# Meaty_3__vPS01.net
KiCad netlist of a schematic drawn in EAGLE
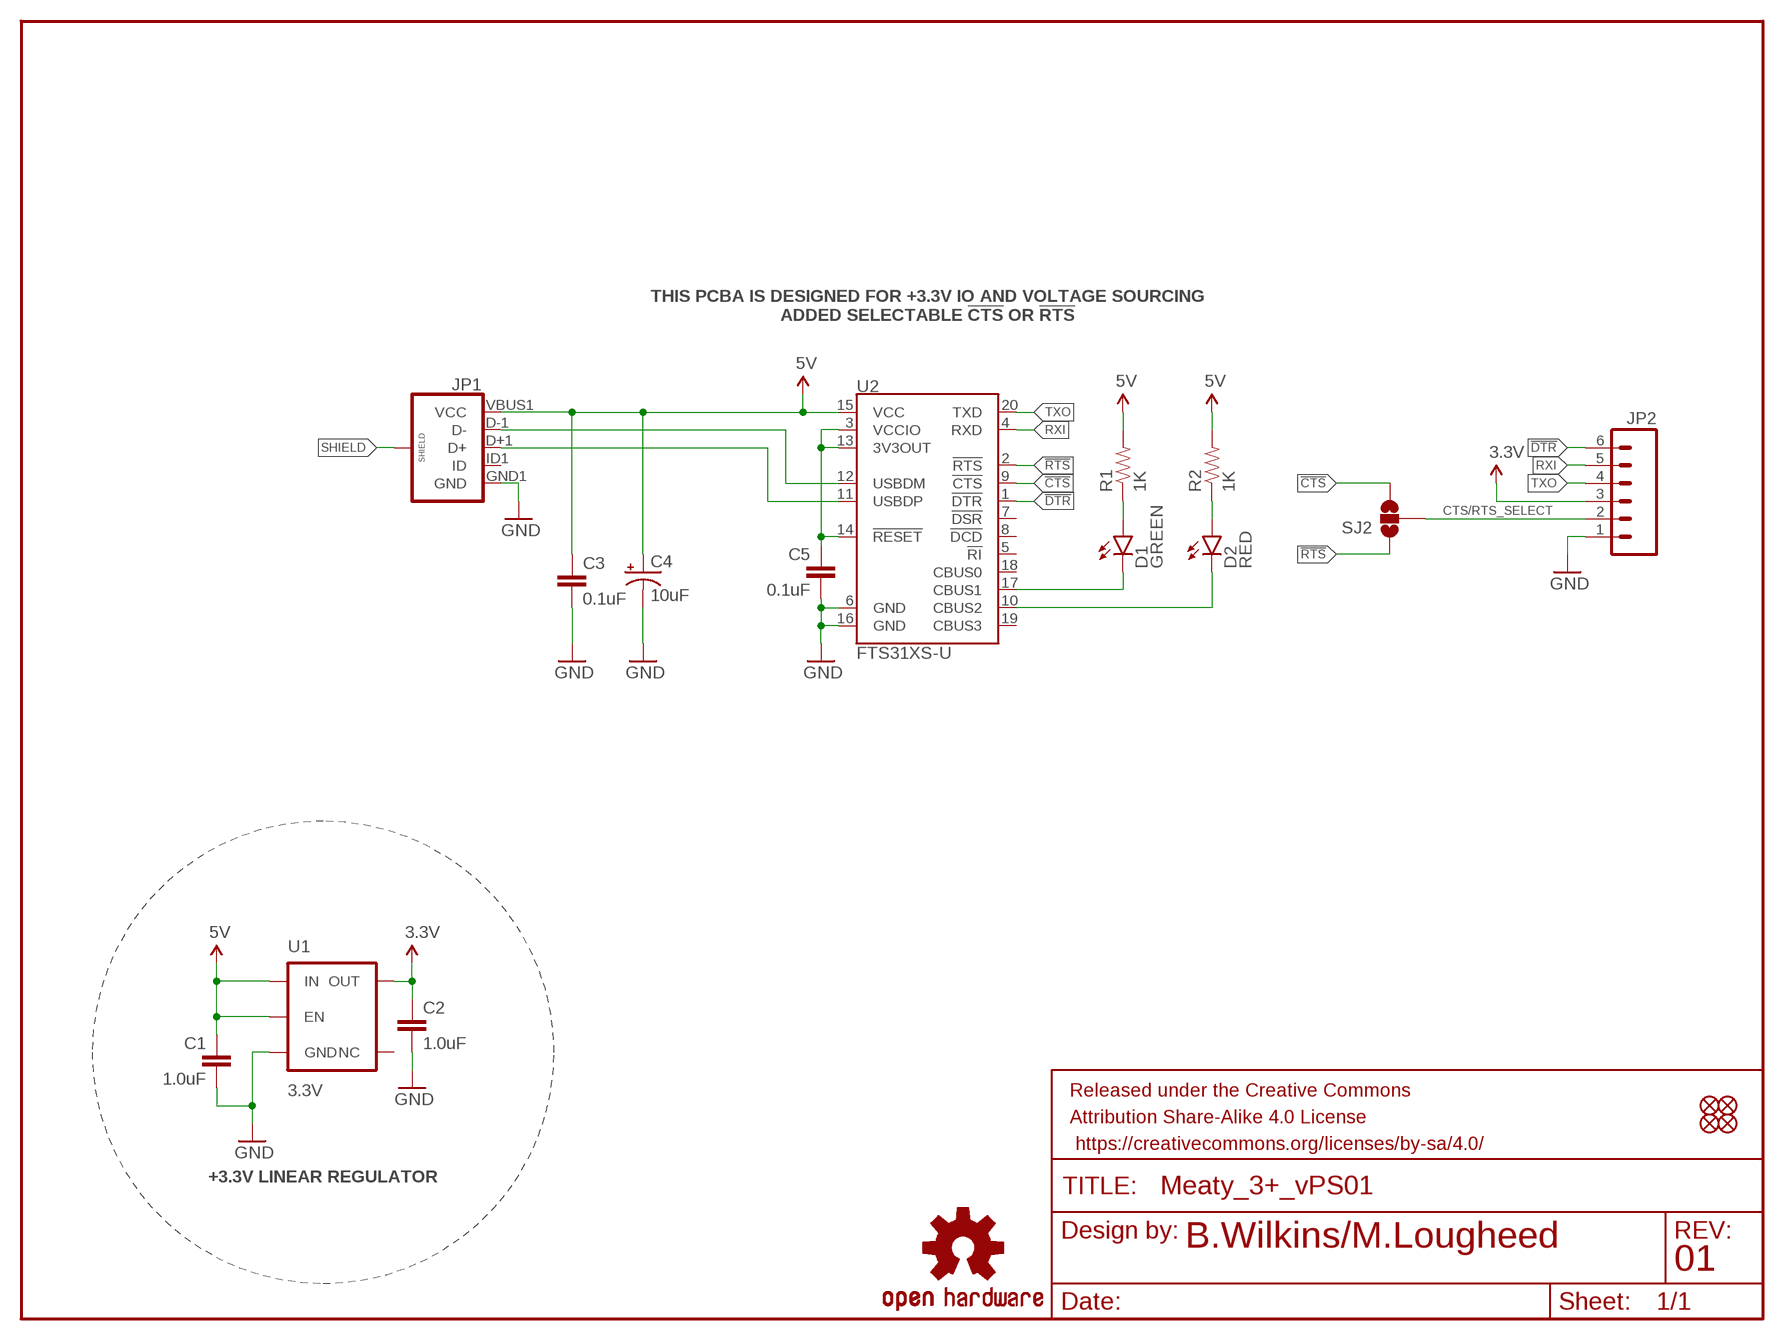
[diagram p0: schematic, sheet 1]

(export (version "E")
  (design (tool "Eeschema 10.0.6"))
  (components
    (comp (ref "C1")
      (value "1.0uF")
      (footprint "eagle-import:0603-CAP")
      (libsource (lib "eagle-import") (part "1.0UF-16V-10%(0603)"))
    )
    (comp (ref "C2")
      (value "1.0uF")
      (footprint "eagle-import:0603-CAP")
      (libsource (lib "eagle-import") (part "1.0UF-16V-10%(0603)"))
    )
    (comp (ref "C3")
      (value "0.1uF")
      (footprint "eagle-import:0603-CAP")
      (libsource (lib "eagle-import") (part "0.1UF-25V(+80/-20%)(0603)"))
    )
    (comp (ref "C4")
      (value "10uF")
      (footprint "eagle-import:EIA3216")
      (libsource (lib "eagle-import") (part "10UF-16V-10%(TANT)"))
    )
    (comp (ref "C5")
      (value "0.1uF")
      (footprint "eagle-import:0603-CAP")
      (libsource (lib "eagle-import") (part "0.1UF-25V(+80/-20%)(0603)"))
    )
    (comp (ref "D1")
      (value "GREEN")
      (footprint "eagle-import:LED-0603")
      (libsource (lib "eagle-import") (part "LED-GREEN0603"))
    )
    (comp (ref "D2")
      (value "RED")
      (footprint "eagle-import:LED-0603")
      (libsource (lib "eagle-import") (part "LED-RED0603"))
    )
    (comp (ref "FRAME1")
      (value "FRAME-LETTER")
      (footprint "eagle-import:CREATIVE_COMMONS")
      (libsource (lib "eagle-import") (part "FRAME-LETTER"))
    )
    (comp (ref "JP1")
      (value "USB_MICROB_PLUGCONN-11752")
      (footprint "eagle-import:USB-B-MICRO-SMD_V03")
      (libsource (lib "eagle-import") (part "USB_MICROB_PLUGCONN-11752"))
    )
    (comp (ref "JP2")
      (value "M06SMD-FEMALE-V2")
      (footprint "eagle-import:1X06-SMD-FEMALE-V2")
      (libsource (lib "eagle-import") (part "M06SMD-FEMALE-V2"))
    )
    (comp (ref "JP3")
      (value "FIDUCIAL1X2")
      (footprint "eagle-import:FIDUCIAL-1X2")
      (libsource (lib "eagle-import") (part "FIDUCIAL1X2"))
    )
    (comp (ref "JP4")
      (value "FIDUCIAL1X2")
      (footprint "eagle-import:FIDUCIAL-1X2")
      (libsource (lib "eagle-import") (part "FIDUCIAL1X2"))
    )
    (comp (ref "JP5")
      (value "FIDUCIAL1X2")
      (footprint "eagle-import:FIDUCIAL-1X2")
      (libsource (lib "eagle-import") (part "FIDUCIAL1X2"))
    )
    (comp (ref "JP6")
      (value "FIDUCIAL1X2")
      (footprint "eagle-import:FIDUCIAL-1X2")
      (libsource (lib "eagle-import") (part "FIDUCIAL1X2"))
    )
    (comp (ref "LOGO1")
      (value "OSHW-LOGOS")
      (footprint "eagle-import:OSHW-LOGO-S")
      (libsource (lib "eagle-import") (part "OSHW-LOGOS"))
    )
    (comp (ref "R1")
      (value "1K")
      (footprint "eagle-import:0603-RES")
      (libsource (lib "eagle-import") (part "1KOHM-1/10W-1%(0603)"))
    )
    (comp (ref "R2")
      (value "1K")
      (footprint "eagle-import:0603-RES")
      (libsource (lib "eagle-import") (part "1KOHM-1/10W-1%(0603)"))
    )
    (comp (ref "SJ2")
      (value "SOLDERJUMPER_2WAYS")
      (footprint "eagle-import:SJ_3")
      (libsource (lib "eagle-import") (part "SOLDERJUMPER_2WAYS"))
    )
    (comp (ref "U1")
      (value "3.3V")
      (footprint "eagle-import:SOT23-5")
      (libsource (lib "eagle-import") (part "V_REG_AP2112K-3.3V"))
    )
    (comp (ref "U2")
      (value "FTS31XS-U")
      (footprint "eagle-import:SSOP20_L")
      (libsource (lib "eagle-import") (part "FT231XS"))
    )
  )
  (nets
    (net (code "1") (name "/CTS{slash}RTS_SELECT") (class "Default")
      (node (ref "JP2") (pin "2") (pinfunction "2_2") (pintype "passive"))
      (node (ref "SJ2") (pin "2") (pinfunction "2_2") (pintype "passive"))
    )
    (net (code "2") (name "/~{CTS}") (class "Default")
      (node (ref "SJ2") (pin "3") (pinfunction "3_3") (pintype "passive"))
      (node (ref "U2") (pin "9") (pinfunction "~{CTS}_9") (pintype "bidirectional"))
    )
    (net (code "3") (name "/~{DTR}") (class "Default")
      (node (ref "JP2") (pin "6") (pinfunction "6_6") (pintype "passive"))
      (node (ref "U2") (pin "1") (pinfunction "~{DTR}_1") (pintype "bidirectional"))
    )
    (net (code "4") (name "/~{RTS}") (class "Default")
      (node (ref "SJ2") (pin "1") (pinfunction "1_1") (pintype "passive"))
      (node (ref "U2") (pin "2") (pinfunction "~{RTS}_2") (pintype "bidirectional"))
    )
    (net (code "5") (name "3.3V") (class "Default")
      (node (ref "C2") (pin "1") (pinfunction "1_1") (pintype "passive"))
      (node (ref "JP2") (pin "3") (pinfunction "3_3") (pintype "passive"))
      (node (ref "U1") (pin "5") (pinfunction "OUT_5") (pintype "passive"))
    )
    (net (code "6") (name "5V") (class "Default")
      (node (ref "C1") (pin "1") (pinfunction "1_1") (pintype "passive"))
      (node (ref "C3") (pin "1") (pinfunction "1_1") (pintype "passive"))
      (node (ref "C4") (pin "A") (pinfunction "+_A") (pintype "passive"))
      (node (ref "JP1") (pin "VBUS1") (pinfunction "VCC_VBUS1") (pintype "bidirectional"))
      (node (ref "R1") (pin "2") (pinfunction "2_2") (pintype "passive"))
      (node (ref "R2") (pin "2") (pinfunction "2_2") (pintype "passive"))
      (node (ref "U1") (pin "1") (pinfunction "IN_1") (pintype "input"))
      (node (ref "U1") (pin "3") (pinfunction "EN_3") (pintype "input"))
      (node (ref "U2") (pin "15") (pinfunction "VCC_15") (pintype "bidirectional"))
    )
    (net (code "7") (name "GND") (class "Default")
      (node (ref "C1") (pin "2") (pinfunction "2_2") (pintype "passive"))
      (node (ref "C2") (pin "2") (pinfunction "2_2") (pintype "passive"))
      (node (ref "C3") (pin "2") (pinfunction "2_2") (pintype "passive"))
      (node (ref "C4") (pin "C") (pinfunction "-_C") (pintype "passive"))
      (node (ref "C5") (pin "2") (pinfunction "2_2") (pintype "passive"))
      (node (ref "JP1") (pin "GND1") (pinfunction "GND_GND1") (pintype "bidirectional"))
      (node (ref "JP2") (pin "1") (pinfunction "1_1") (pintype "passive"))
      (node (ref "U1") (pin "2") (pinfunction "GND_2") (pintype "input"))
      (node (ref "U2") (pin "16") (pinfunction "GND_16") (pintype "bidirectional"))
      (node (ref "U2") (pin "6") (pinfunction "GND_6") (pintype "bidirectional"))
    )
    (net (code "8") (name "Net-(D1-PadA)") (class "Default")
      (node (ref "D1") (pin "A") (pinfunction "A_A") (pintype "passive"))
      (node (ref "R1") (pin "1") (pinfunction "1_1") (pintype "passive"))
    )
    (net (code "9") (name "Net-(D2-PadA)") (class "Default")
      (node (ref "D2") (pin "A") (pinfunction "A_A") (pintype "passive"))
      (node (ref "R2") (pin "1") (pinfunction "1_1") (pintype "passive"))
    )
    (net (code "10") (name "Net-(JP1-D+)") (class "Default")
      (node (ref "JP1") (pin "D+1") (pinfunction "D+_D+1") (pintype "bidirectional"))
      (node (ref "U2") (pin "11") (pinfunction "USBDP_11") (pintype "bidirectional"))
    )
    (net (code "11") (name "Net-(JP1-D-)") (class "Default")
      (node (ref "JP1") (pin "D-1") (pinfunction "D-_D-1") (pintype "bidirectional"))
      (node (ref "U2") (pin "12") (pinfunction "USBDM_12") (pintype "bidirectional"))
    )
    (net (code "12") (name "Net-(U2-3V3OUT)") (class "Default")
      (node (ref "C5") (pin "1") (pinfunction "1_1") (pintype "passive"))
      (node (ref "U2") (pin "13") (pinfunction "3V3OUT_13") (pintype "bidirectional"))
      (node (ref "U2") (pin "14") (pinfunction "~{RESET}_14") (pintype "bidirectional"))
      (node (ref "U2") (pin "3") (pinfunction "VCCIO_3") (pintype "bidirectional"))
    )
    (net (code "13") (name "Net-(U2-CBUS1)") (class "Default")
      (node (ref "D1") (pin "C") (pinfunction "C_C") (pintype "passive"))
      (node (ref "U2") (pin "17") (pinfunction "CBUS1_17") (pintype "bidirectional"))
    )
    (net (code "14") (name "Net-(U2-CBUS2)") (class "Default")
      (node (ref "D2") (pin "C") (pinfunction "C_C") (pintype "passive"))
      (node (ref "U2") (pin "10") (pinfunction "CBUS2_10") (pintype "bidirectional"))
    )
    (net (code "15") (name "RXI") (class "Default")
      (node (ref "JP2") (pin "5") (pinfunction "5_5") (pintype "passive"))
      (node (ref "U2") (pin "4") (pinfunction "RXD_4") (pintype "bidirectional"))
    )
    (net (code "16") (name "SHIELD") (class "Default")
      (node (ref "JP1") (pin "SHIELD1") (pinfunction "SHIELD_SHIELD1") (pintype "bidirectional"))
      (node (ref "JP1") (pin "SHIELD2") (pinfunction "SHIELD_SHIELD2") (pintype "bidirectional"))
      (node (ref "JP1") (pin "SHIELD3") (pinfunction "SHIELD_SHIELD3") (pintype "bidirectional"))
    )
    (net (code "17") (name "TXO") (class "Default")
      (node (ref "JP2") (pin "4") (pinfunction "4_4") (pintype "passive"))
      (node (ref "U2") (pin "20") (pinfunction "TXD_20") (pintype "bidirectional"))
    )
    (net (code "18") (name "unconnected-(JP1-ID-PadID1)") (class "Default")
      (node (ref "JP1") (pin "ID1") (pinfunction "ID_ID1") (pintype "bidirectional"))
    )
    (net (code "19") (name "unconnected-(U1-NC-Pad4)") (class "Default")
      (node (ref "U1") (pin "4") (pinfunction "NC_4") (pintype "input"))
    )
    (net (code "20") (name "unconnected-(U2-CBUS0-Pad18)") (class "Default")
      (node (ref "U2") (pin "18") (pinfunction "CBUS0_18") (pintype "bidirectional"))
    )
    (net (code "21") (name "unconnected-(U2-CBUS3-Pad19)") (class "Default")
      (node (ref "U2") (pin "19") (pinfunction "CBUS3_19") (pintype "bidirectional"))
    )
    (net (code "22") (name "unconnected-(U2-~{DCD}-Pad8)") (class "Default")
      (node (ref "U2") (pin "8") (pinfunction "~{DCD}_8") (pintype "bidirectional"))
    )
    (net (code "23") (name "unconnected-(U2-~{DSR}-Pad7)") (class "Default")
      (node (ref "U2") (pin "7") (pinfunction "~{DSR}_7") (pintype "bidirectional"))
    )
    (net (code "24") (name "unconnected-(U2-~{RI}-Pad5)") (class "Default")
      (node (ref "U2") (pin "5") (pinfunction "~{RI}_5") (pintype "bidirectional"))
    )
  )
)
